# controller.net
KiCad netlist of a schematic drawn in EAGLE
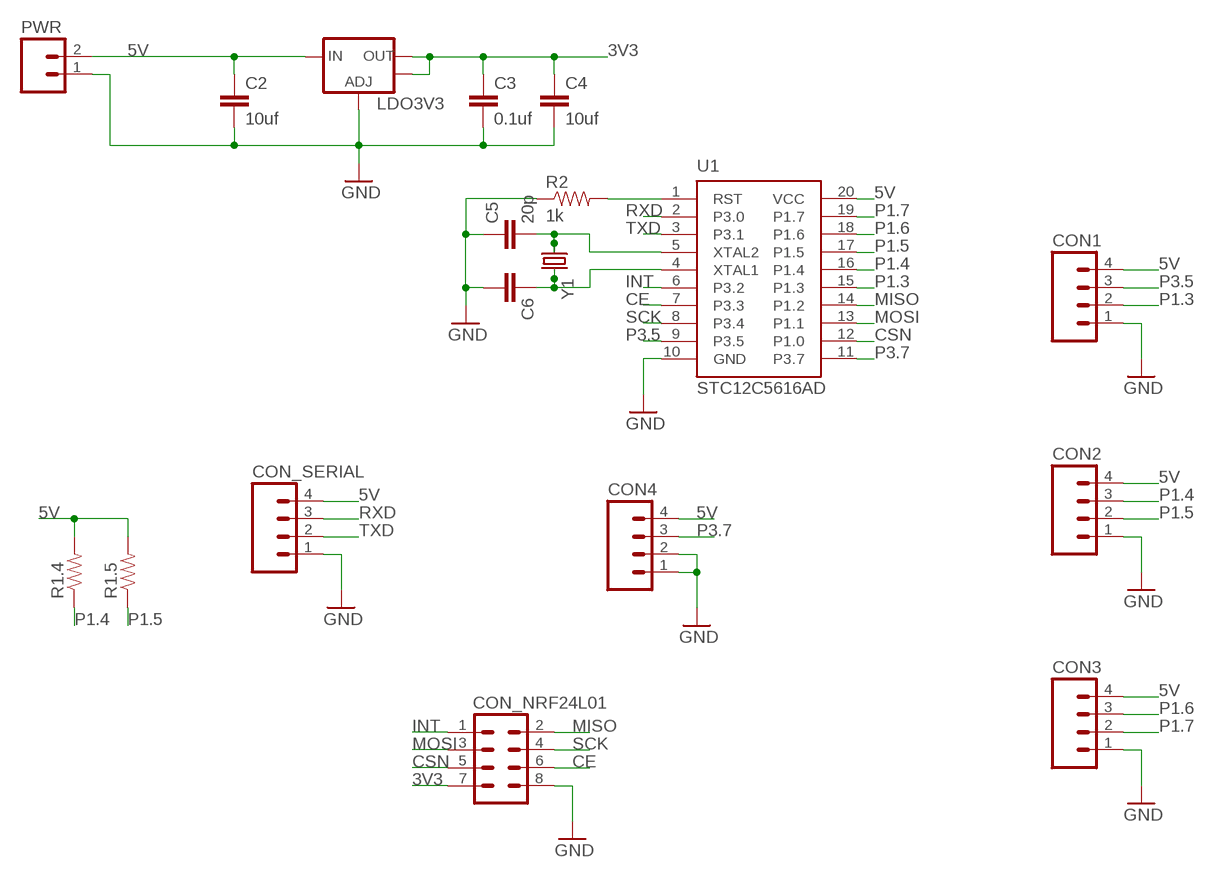
[diagram p0: schematic, sheet 1]

(export (version "E")
  (design (tool "Eeschema 10.0.6"))
  (components
    (comp (ref "C2")
      (value "10uf")
      (footprint "eagle-import:0805")
      (libsource (lib "eagle-import") (part "CAP0805"))
    )
    (comp (ref "C3")
      (value "0.1uf")
      (footprint "eagle-import:0805")
      (libsource (lib "eagle-import") (part "CAP0805"))
    )
    (comp (ref "C4")
      (value "10uf")
      (footprint "eagle-import:0805")
      (libsource (lib "eagle-import") (part "CAP0805"))
    )
    (comp (ref "C5")
      (value "20p")
      (footprint "eagle-import:0603-CAP")
      (libsource (lib "eagle-import") (part "CAP0603-CAP"))
    )
    (comp (ref "C6")
      (value "CAP0603-CAP")
      (footprint "eagle-import:0603-CAP")
      (libsource (lib "eagle-import") (part "CAP0603-CAP"))
    )
    (comp (ref "CON1")
      (value "M04PTH")
      (footprint "eagle-import:1X04")
      (libsource (lib "eagle-import") (part "M04PTH"))
    )
    (comp (ref "CON2")
      (value "M04PTH")
      (footprint "eagle-import:1X04")
      (libsource (lib "eagle-import") (part "M04PTH"))
    )
    (comp (ref "CON3")
      (value "M04PTH")
      (footprint "eagle-import:1X04")
      (libsource (lib "eagle-import") (part "M04PTH"))
    )
    (comp (ref "CON4")
      (value "M04PTH")
      (footprint "eagle-import:1X04")
      (libsource (lib "eagle-import") (part "M04PTH"))
    )
    (comp (ref "CON_NRF24L01")
      (value "M04X2")
      (footprint "eagle-import:2X4")
      (libsource (lib "eagle-import") (part "M04X2"))
    )
    (comp (ref "CON_SERIAL")
      (value "M04PTH")
      (footprint "eagle-import:1X04")
      (libsource (lib "eagle-import") (part "M04PTH"))
    )
    (comp (ref "LDO3V3")
      (value "V_REG_LM1117SOT223")
      (footprint "eagle-import:SOT223")
      (libsource (lib "eagle-import") (part "V_REG_LM1117SOT223"))
    )
    (comp (ref "PWR")
      (value "M02PTH")
      (footprint "eagle-import:1X02")
      (libsource (lib "eagle-import") (part "M02PTH"))
    )
    (comp (ref "R1.4")
      (value "RESISTOR0805-RES")
      (footprint "eagle-import:0805")
      (libsource (lib "eagle-import") (part "RESISTOR0805-RES"))
    )
    (comp (ref "R1.5")
      (value "RESISTOR0805-RES")
      (footprint "eagle-import:0805")
      (libsource (lib "eagle-import") (part "RESISTOR0805-RES"))
    )
    (comp (ref "R2")
      (value "1k")
      (footprint "eagle-import:0805")
      (libsource (lib "eagle-import") (part "RESISTOR0805-RES"))
    )
    (comp (ref "U1")
      (value "STC12C5616AD")
      (footprint "eagle-import:SOP20")
      (libsource (lib "eagle-import") (part "STC12C5616AD"))
    )
    (comp (ref "Y1")
      (value "CRYSTALHC49US")
      (footprint "eagle-import:HC49US")
      (libsource (lib "eagle-import") (part "CRYSTALHC49US"))
    )
  )
  (nets
    (net (code "1") (name "/3V3") (class "Default")
      (node (ref "C3") (pin "1") (pinfunction "1_1") (pintype "passive"))
      (node (ref "C4") (pin "1") (pinfunction "1_1") (pintype "passive"))
      (node (ref "CON_NRF24L01") (pin "7") (pinfunction "7_7") (pintype "passive"))
      (node (ref "LDO3V3") (pin "2") (pinfunction "OUT_2") (pintype "output"))
      (node (ref "LDO3V3") (pin "4") (pinfunction "OUT_4") (pintype "output"))
    )
    (net (code "2") (name "/5V") (class "Default")
      (node (ref "C2") (pin "1") (pinfunction "1_1") (pintype "passive"))
      (node (ref "CON1") (pin "4") (pinfunction "4_4") (pintype "passive"))
      (node (ref "CON2") (pin "4") (pinfunction "4_4") (pintype "passive"))
      (node (ref "CON3") (pin "4") (pinfunction "4_4") (pintype "passive"))
      (node (ref "CON4") (pin "4") (pinfunction "4_4") (pintype "passive"))
      (node (ref "CON_SERIAL") (pin "4") (pinfunction "4_4") (pintype "passive"))
      (node (ref "LDO3V3") (pin "3") (pinfunction "IN_3") (pintype "input"))
      (node (ref "PWR") (pin "2") (pinfunction "2_2") (pintype "passive"))
      (node (ref "R1.4") (pin "2") (pinfunction "2_2") (pintype "passive"))
      (node (ref "R1.5") (pin "2") (pinfunction "2_2") (pintype "passive"))
      (node (ref "U1") (pin "20") (pinfunction "VCC_20") (pintype "bidirectional"))
    )
    (net (code "3") (name "/CE") (class "Default")
      (node (ref "CON_NRF24L01") (pin "6") (pinfunction "6_6") (pintype "passive"))
      (node (ref "U1") (pin "7") (pinfunction "P3.3_7") (pintype "bidirectional"))
    )
    (net (code "4") (name "/CSN") (class "Default")
      (node (ref "CON_NRF24L01") (pin "5") (pinfunction "5_5") (pintype "passive"))
      (node (ref "U1") (pin "12") (pinfunction "P1.0_12") (pintype "bidirectional"))
    )
    (net (code "5") (name "/INT") (class "Default")
      (node (ref "CON_NRF24L01") (pin "1") (pinfunction "1_1") (pintype "passive"))
      (node (ref "U1") (pin "6") (pinfunction "P3.2_6") (pintype "bidirectional"))
    )
    (net (code "6") (name "/MISO") (class "Default")
      (node (ref "CON_NRF24L01") (pin "2") (pinfunction "2_2") (pintype "passive"))
      (node (ref "U1") (pin "14") (pinfunction "P1.2_14") (pintype "bidirectional"))
    )
    (net (code "7") (name "/MOSI") (class "Default")
      (node (ref "CON_NRF24L01") (pin "3") (pinfunction "3_3") (pintype "passive"))
      (node (ref "U1") (pin "13") (pinfunction "P1.1_13") (pintype "bidirectional"))
    )
    (net (code "8") (name "/P1.3") (class "Default")
      (node (ref "CON1") (pin "2") (pinfunction "2_2") (pintype "passive"))
      (node (ref "U1") (pin "15") (pinfunction "P1.3_15") (pintype "bidirectional"))
    )
    (net (code "9") (name "/P1.4") (class "Default")
      (node (ref "CON2") (pin "3") (pinfunction "3_3") (pintype "passive"))
      (node (ref "R1.4") (pin "1") (pinfunction "1_1") (pintype "passive"))
      (node (ref "U1") (pin "16") (pinfunction "P1.4_16") (pintype "bidirectional"))
    )
    (net (code "10") (name "/P1.5") (class "Default")
      (node (ref "CON2") (pin "2") (pinfunction "2_2") (pintype "passive"))
      (node (ref "R1.5") (pin "1") (pinfunction "1_1") (pintype "passive"))
      (node (ref "U1") (pin "17") (pinfunction "P1.5_17") (pintype "bidirectional"))
    )
    (net (code "11") (name "/P1.6") (class "Default")
      (node (ref "CON3") (pin "3") (pinfunction "3_3") (pintype "passive"))
      (node (ref "U1") (pin "18") (pinfunction "P1.6_18") (pintype "bidirectional"))
    )
    (net (code "12") (name "/P1.7") (class "Default")
      (node (ref "CON3") (pin "2") (pinfunction "2_2") (pintype "passive"))
      (node (ref "U1") (pin "19") (pinfunction "P1.7_19") (pintype "bidirectional"))
    )
    (net (code "13") (name "/P3.5") (class "Default")
      (node (ref "CON1") (pin "3") (pinfunction "3_3") (pintype "passive"))
      (node (ref "U1") (pin "9") (pinfunction "P3.5_9") (pintype "bidirectional"))
    )
    (net (code "14") (name "/P3.7") (class "Default")
      (node (ref "CON4") (pin "3") (pinfunction "3_3") (pintype "passive"))
      (node (ref "U1") (pin "11") (pinfunction "P3.7_11") (pintype "bidirectional"))
    )
    (net (code "15") (name "/RXD") (class "Default")
      (node (ref "CON_SERIAL") (pin "3") (pinfunction "3_3") (pintype "passive"))
      (node (ref "U1") (pin "2") (pinfunction "P3.0_2") (pintype "bidirectional"))
    )
    (net (code "16") (name "/SCK") (class "Default")
      (node (ref "CON_NRF24L01") (pin "4") (pinfunction "4_4") (pintype "passive"))
      (node (ref "U1") (pin "8") (pinfunction "P3.4_8") (pintype "bidirectional"))
    )
    (net (code "17") (name "/TXD") (class "Default")
      (node (ref "CON_SERIAL") (pin "2") (pinfunction "2_2") (pintype "passive"))
      (node (ref "U1") (pin "3") (pinfunction "P3.1_3") (pintype "bidirectional"))
    )
    (net (code "18") (name "GND") (class "Default")
      (node (ref "C2") (pin "2") (pinfunction "2_2") (pintype "passive"))
      (node (ref "C3") (pin "2") (pinfunction "2_2") (pintype "passive"))
      (node (ref "C4") (pin "2") (pinfunction "2_2") (pintype "passive"))
      (node (ref "C5") (pin "1") (pinfunction "1_1") (pintype "passive"))
      (node (ref "C6") (pin "2") (pinfunction "2_2") (pintype "passive"))
      (node (ref "CON1") (pin "1") (pinfunction "1_1") (pintype "passive"))
      (node (ref "CON2") (pin "1") (pinfunction "1_1") (pintype "passive"))
      (node (ref "CON3") (pin "1") (pinfunction "1_1") (pintype "passive"))
      (node (ref "CON4") (pin "1") (pinfunction "1_1") (pintype "passive"))
      (node (ref "CON4") (pin "2") (pinfunction "2_2") (pintype "passive"))
      (node (ref "CON_NRF24L01") (pin "8") (pinfunction "8_8") (pintype "passive"))
      (node (ref "CON_SERIAL") (pin "1") (pinfunction "1_1") (pintype "passive"))
      (node (ref "LDO3V3") (pin "1") (pinfunction "ADJ_1") (pintype "input"))
      (node (ref "PWR") (pin "1") (pinfunction "1_1") (pintype "passive"))
      (node (ref "R2") (pin "1") (pinfunction "1_1") (pintype "passive"))
      (node (ref "U1") (pin "10") (pinfunction "GND_10") (pintype "bidirectional"))
    )
    (net (code "19") (name "Net-(U1-RST)") (class "Default")
      (node (ref "R2") (pin "2") (pinfunction "2_2") (pintype "passive"))
      (node (ref "U1") (pin "1") (pinfunction "RST_1") (pintype "bidirectional"))
    )
    (net (code "20") (name "Net-(U1-XTAL1)") (class "Default")
      (node (ref "C6") (pin "1") (pinfunction "1_1") (pintype "passive"))
      (node (ref "U1") (pin "4") (pinfunction "XTAL1_4") (pintype "bidirectional"))
      (node (ref "Y1") (pin "2") (pinfunction "2_2") (pintype "passive"))
    )
    (net (code "21") (name "Net-(U1-XTAL2)") (class "Default")
      (node (ref "C5") (pin "2") (pinfunction "2_2") (pintype "passive"))
      (node (ref "U1") (pin "5") (pinfunction "XTAL2_5") (pintype "bidirectional"))
      (node (ref "Y1") (pin "1") (pinfunction "1_1") (pintype "passive"))
    )
  )
)
